# uLI-00.net
KiCad netlist of a schematic drawn in EAGLE
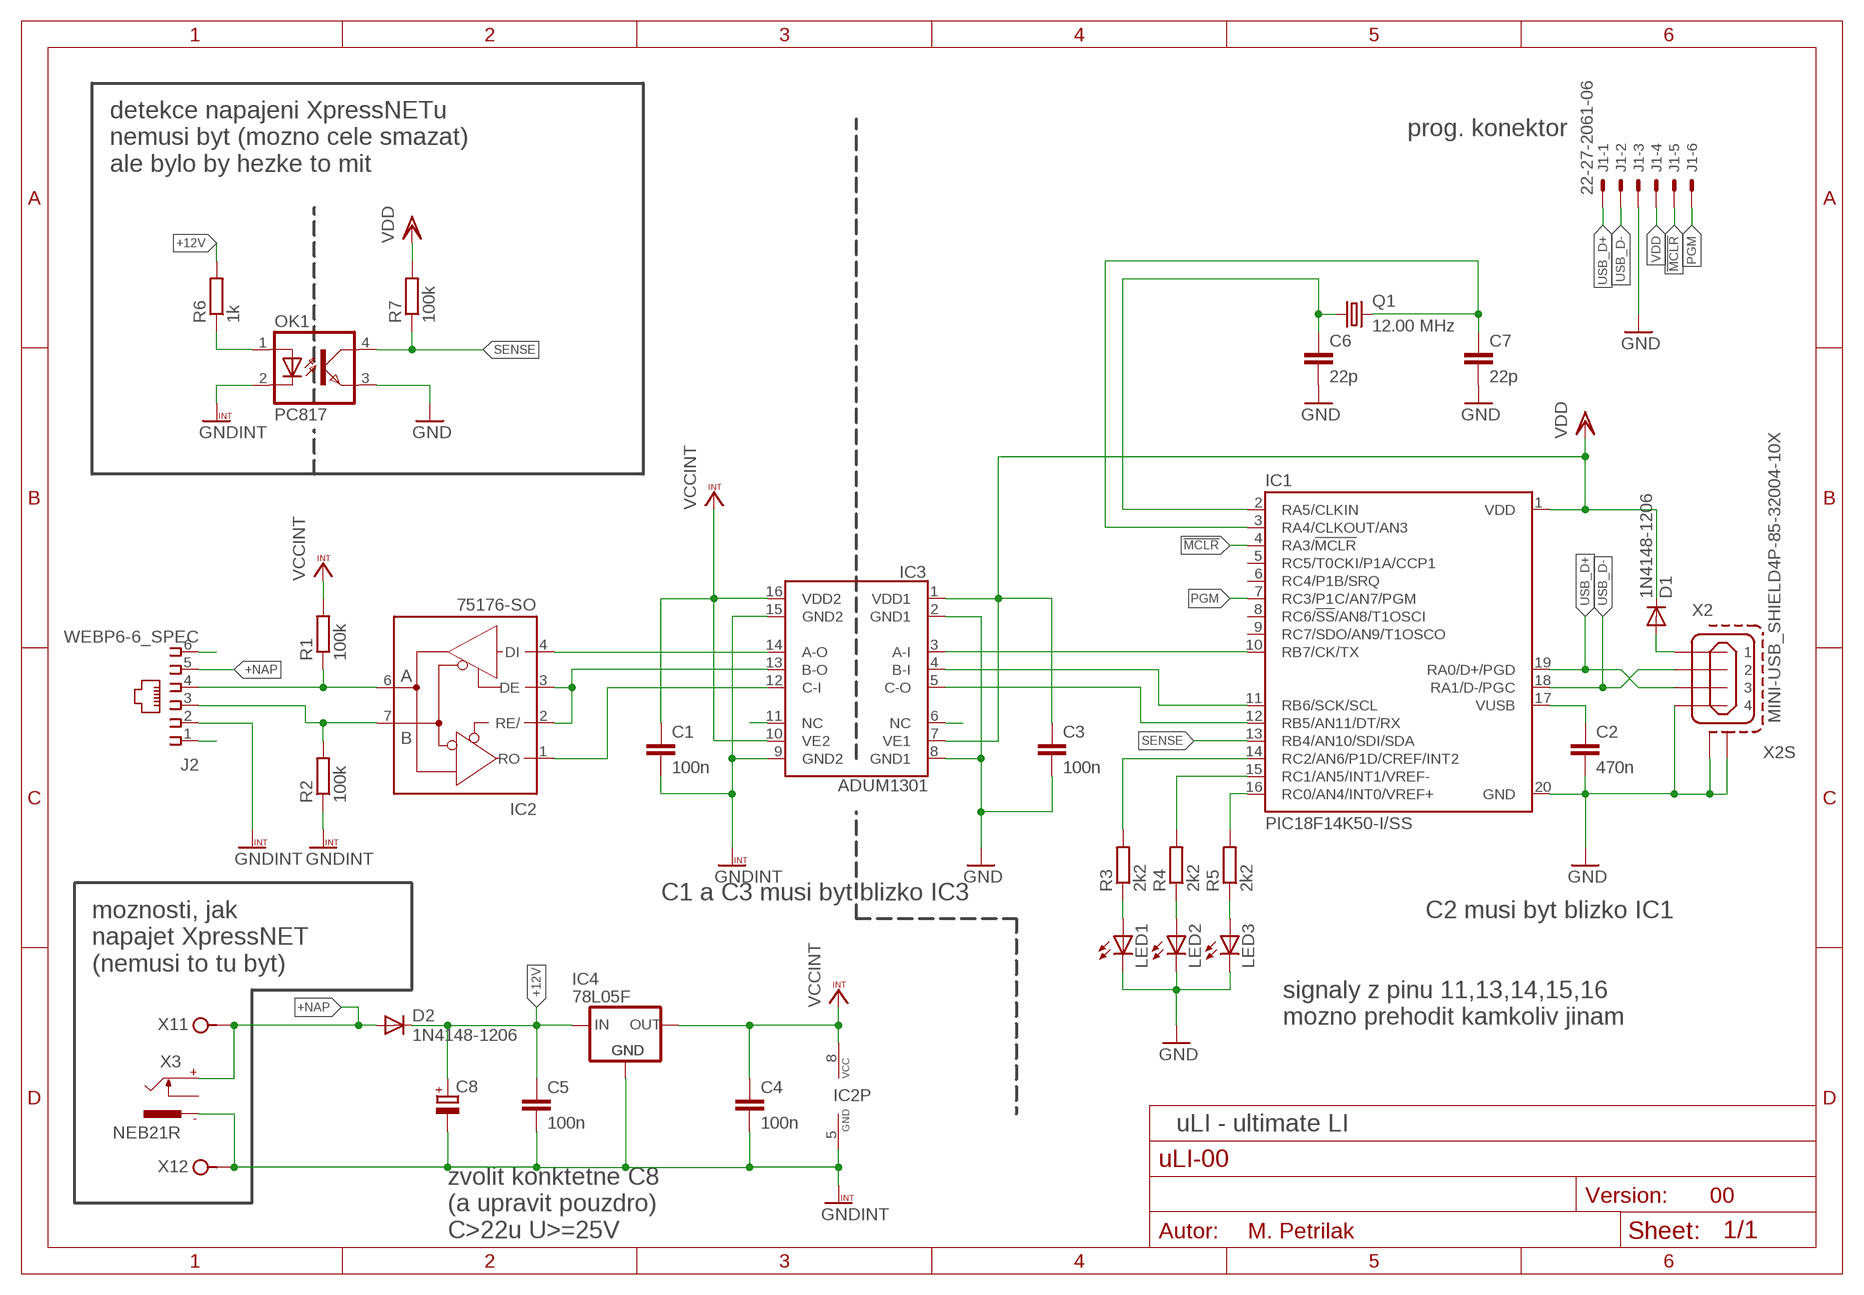
[diagram p0: schematic, sheet 1]

(export (version "E")
  (design (tool "Eeschema 10.0.6"))
  (components
    (comp (ref "C1")
      (value "100n")
      (footprint "eagle-import:C1206")
      (libsource (lib "eagle-import") (part "C-EUC1206"))
    )
    (comp (ref "C2")
      (value "470n")
      (footprint "eagle-import:C1206")
      (libsource (lib "eagle-import") (part "C-EUC1206"))
    )
    (comp (ref "C3")
      (value "100n")
      (footprint "eagle-import:C1206")
      (libsource (lib "eagle-import") (part "C-EUC1206"))
    )
    (comp (ref "C4")
      (value "100n")
      (footprint "eagle-import:C1206")
      (libsource (lib "eagle-import") (part "C-EUC1206"))
    )
    (comp (ref "C5")
      (value "100n")
      (footprint "eagle-import:C1206")
      (libsource (lib "eagle-import") (part "C-EUC1206"))
    )
    (comp (ref "C6")
      (value "22p")
      (footprint "eagle-import:C0805")
      (libsource (lib "eagle-import") (part "C-EUC0805"))
    )
    (comp (ref "C7")
      (value "22p")
      (footprint "eagle-import:C0805")
      (libsource (lib "eagle-import") (part "C-EUC0805"))
    )
    (comp (ref "C8")
      (value "CPOL-EUE3.5-8L")
      (footprint "eagle-import:E3,5-8L")
      (libsource (lib "eagle-import") (part "CPOL-EUE3.5-8L"))
    )
    (comp (ref "D1")
      (value "1N4148-1206")
      (footprint "eagle-import:D1206")
      (libsource (lib "eagle-import") (part "1N4148-1206"))
    )
    (comp (ref "D2")
      (value "1N4148-1206")
      (footprint "eagle-import:D1206")
      (libsource (lib "eagle-import") (part "1N4148-1206"))
    )
    (comp (ref "IC1")
      (value "PIC18F14K50-I/SS")
      (footprint "eagle-import:SSOP20")
      (libsource (lib "eagle-import") (part "PIC18K50-I/SSF14"))
    )
    (comp (ref "IC2")
      (value "75176-SO")
      (footprint "eagle-import:SO08")
      (libsource (lib "eagle-import") (part "75176-SO"))
    )
    (comp (ref "IC3")
      (value "ADUM1301")
      (footprint "eagle-import:SO-16W")
      (libsource (lib "eagle-import") (part "ADUM1301"))
    )
    (comp (ref "IC4")
      (value "78L05F")
      (footprint "eagle-import:SOT89")
      (libsource (lib "eagle-import") (part "78LF05"))
    )
    (comp (ref "J1")
      (value "22-27-2061-06")
      (footprint "eagle-import:6410-06")
      (libsource (lib "eagle-import") (part "22-?-0627-2061"))
    )
    (comp (ref "J2")
      (value "WEBP6-6_SPEC")
      (footprint "eagle-import:WEBP6-6_SPEC")
      (libsource (lib "eagle-import") (part "WEBP6-6_SPEC"))
    )
    (comp (ref "LED1")
      (value "LED3MM")
      (footprint "eagle-import:LED3MM")
      (libsource (lib "eagle-import") (part "LED3MM"))
    )
    (comp (ref "LED2")
      (value "LED3MM")
      (footprint "eagle-import:LED3MM")
      (libsource (lib "eagle-import") (part "LED3MM"))
    )
    (comp (ref "LED3")
      (value "LED3MM")
      (footprint "eagle-import:LED3MM")
      (libsource (lib "eagle-import") (part "LED3MM"))
    )
    (comp (ref "OK1")
      (value "PC817")
      (footprint "eagle-import:DIL04")
      (libsource (lib "eagle-import") (part "PC817"))
    )
    (comp (ref "Q1")
      (value "12.00 MHz")
      (footprint "eagle-import:HC49U70")
      (libsource (lib "eagle-import") (part "XTAL"))
    )
    (comp (ref "R1")
      (value "100k")
      (footprint "eagle-import:R1206")
      (libsource (lib "eagle-import") (part "R-EU_R1206"))
    )
    (comp (ref "R2")
      (value "100k")
      (footprint "eagle-import:R1206")
      (libsource (lib "eagle-import") (part "R-EU_R1206"))
    )
    (comp (ref "R3")
      (value "2k2")
      (footprint "eagle-import:R1206")
      (libsource (lib "eagle-import") (part "R-EU_R1206"))
    )
    (comp (ref "R4")
      (value "2k2")
      (footprint "eagle-import:R1206")
      (libsource (lib "eagle-import") (part "R-EU_R1206"))
    )
    (comp (ref "R5")
      (value "2k2")
      (footprint "eagle-import:R1206")
      (libsource (lib "eagle-import") (part "R-EU_R1206"))
    )
    (comp (ref "R6")
      (value "1k")
      (footprint "eagle-import:R1206")
      (libsource (lib "eagle-import") (part "R-EU_R1206"))
    )
    (comp (ref "R7")
      (value "100k")
      (footprint "eagle-import:R1206")
      (libsource (lib "eagle-import") (part "R-EU_R1206"))
    )
    (comp (ref "X1")
      (value "ARK1550/2")
      (footprint "eagle-import:ARK1550_2")
      (libsource (lib "eagle-import") (part "ARK1550/2"))
    )
    (comp (ref "X2")
      (value "MINI-USB_SHIELD4P-85-32004-10X")
      (footprint "eagle-import:85-32004-10X")
      (libsource (lib "eagle-import") (part "MINI-USB_SHIELD4P-85-32004-10X"))
    )
    (comp (ref "X3")
      (value "NEB21R")
      (footprint "eagle-import:NEB21R")
      (libsource (lib "eagle-import") (part "NEB21R"))
    )
  )
  (nets
    (net (code "1") (name "+12V") (class "Default")
      (node (ref "C5") (pin "1") (pinfunction "1_1") (pintype "passive"))
      (node (ref "C8") (pin "+") (pinfunction "+_+") (pintype "passive"))
      (node (ref "D2") (pin "C") (pinfunction "C_C") (pintype "passive"))
      (node (ref "IC4") (pin "3") (pinfunction "VI_3") (pintype "input"))
      (node (ref "R6") (pin "2") (pinfunction "2_2") (pintype "passive"))
    )
    (net (code "2") (name "+NAP") (class "Default")
      (node (ref "D2") (pin "A") (pinfunction "A_A") (pintype "passive"))
      (node (ref "J2") (pin "5") (pinfunction "5_5") (pintype "passive"))
      (node (ref "X1") (pin "1") (pinfunction "1_1") (pintype "passive"))
      (node (ref "X3") (pin "+") (pinfunction "+_+") (pintype "passive"))
    )
    (net (code "3") (name "/~{MCLR}") (class "Default")
      (node (ref "IC1") (pin "4") (pinfunction "RA3/~{MCLR}_4") (pintype "bidirectional"))
      (node (ref "J1") (pin "5") (pinfunction "S_5") (pintype "passive"))
    )
    (net (code "4") (name "GND") (class "Default")
      (node (ref "C2") (pin "2") (pinfunction "2_2") (pintype "passive"))
      (node (ref "C3") (pin "2") (pinfunction "2_2") (pintype "passive"))
      (node (ref "C6") (pin "2") (pinfunction "2_2") (pintype "passive"))
      (node (ref "C7") (pin "2") (pinfunction "2_2") (pintype "passive"))
      (node (ref "IC1") (pin "20") (pinfunction "GND_20") (pintype "power_in"))
      (node (ref "IC3") (pin "2") (pinfunction "GND1_2") (pintype "power_in"))
      (node (ref "IC3") (pin "8") (pinfunction "GND1_8") (pintype "power_in"))
      (node (ref "J1") (pin "3") (pinfunction "S_3") (pintype "passive"))
      (node (ref "LED1") (pin "K") (pinfunction "C_K") (pintype "passive"))
      (node (ref "LED2") (pin "K") (pinfunction "C_K") (pintype "passive"))
      (node (ref "LED3") (pin "K") (pinfunction "C_K") (pintype "passive"))
      (node (ref "OK1") (pin "3") (pinfunction "EMIT_3") (pintype "passive"))
      (node (ref "X2") (pin "4") (pinfunction "4_4") (pintype "passive"))
      (node (ref "X2") (pin "M1") (pinfunction "S1_M1") (pintype "passive"))
      (node (ref "X2") (pin "M2") (pinfunction "S2_M2") (pintype "passive"))
    )
    (net (code "5") (name "GNDINT") (class "Default")
      (node (ref "C1") (pin "2") (pinfunction "2_2") (pintype "passive"))
      (node (ref "C4") (pin "2") (pinfunction "2_2") (pintype "passive"))
      (node (ref "C5") (pin "2") (pinfunction "2_2") (pintype "passive"))
      (node (ref "C8") (pin "-") (pinfunction "-_-") (pintype "passive"))
      (node (ref "IC2") (pin "5") (pinfunction "GND_5") (pintype "power_in"))
      (node (ref "IC3") (pin "15") (pinfunction "GND2_15") (pintype "power_in"))
      (node (ref "IC3") (pin "9") (pinfunction "GND2_9") (pintype "power_in"))
      (node (ref "IC4") (pin "2") (pinfunction "GND_2") (pintype "passive"))
      (node (ref "IC4") (pin "2@1") (pinfunction "GND_2@1") (pintype "passive"))
      (node (ref "J2") (pin "2") (pinfunction "2_2") (pintype "passive"))
      (node (ref "OK1") (pin "2") (pinfunction "C_2") (pintype "passive"))
      (node (ref "R2") (pin "1") (pinfunction "1_1") (pintype "passive"))
      (node (ref "X1") (pin "2") (pinfunction "1_2") (pintype "passive"))
      (node (ref "X3") (pin "-") (pinfunction "-_-") (pintype "passive"))
    )
    (net (code "6") (name "Net-(D1-PadA)") (class "Default")
      (node (ref "D1") (pin "A") (pinfunction "A_A") (pintype "passive"))
      (node (ref "X2") (pin "1") (pinfunction "1_1") (pintype "passive"))
    )
    (net (code "7") (name "Net-(IC1-RA4{slash}CLKOUT{slash}AN3)") (class "Default")
      (node (ref "C7") (pin "1") (pinfunction "1_1") (pintype "passive"))
      (node (ref "IC1") (pin "3") (pinfunction "RA4/CLKOUT/AN3_3") (pintype "bidirectional"))
      (node (ref "Q1") (pin "2") (pinfunction "2_2") (pintype "passive"))
    )
    (net (code "8") (name "Net-(IC1-RA5{slash}CLKIN)") (class "Default")
      (node (ref "C6") (pin "1") (pinfunction "1_1") (pintype "passive"))
      (node (ref "IC1") (pin "2") (pinfunction "RA5/CLKIN_2") (pintype "bidirectional"))
      (node (ref "Q1") (pin "1") (pinfunction "1_1") (pintype "passive"))
    )
    (net (code "9") (name "Net-(IC1-RB5{slash}AN11{slash}DT{slash}RX)") (class "Default")
      (node (ref "IC1") (pin "12") (pinfunction "RB5/AN11/DT/RX_12") (pintype "bidirectional"))
      (node (ref "IC3") (pin "5") (pinfunction "C-O_5") (pintype "output"))
    )
    (net (code "10") (name "Net-(IC1-RB6{slash}SCK{slash}SCL)") (class "Default")
      (node (ref "IC1") (pin "11") (pinfunction "RB6/SCK/SCL_11") (pintype "bidirectional"))
      (node (ref "IC3") (pin "4") (pinfunction "B-I_4") (pintype "input"))
    )
    (net (code "11") (name "Net-(IC1-RB7{slash}CK{slash}TX)") (class "Default")
      (node (ref "IC1") (pin "10") (pinfunction "RB7/CK/TX_10") (pintype "bidirectional"))
      (node (ref "IC3") (pin "3") (pinfunction "A-I_3") (pintype "input"))
    )
    (net (code "12") (name "Net-(IC1-RC0{slash}AN4{slash}INT0{slash}VREF+)") (class "Default")
      (node (ref "IC1") (pin "16") (pinfunction "RC0/AN4/INT0/VREF+_16") (pintype "bidirectional"))
      (node (ref "R5") (pin "2") (pinfunction "2_2") (pintype "passive"))
    )
    (net (code "13") (name "Net-(IC1-RC1{slash}AN5{slash}INT1{slash}VREF-)") (class "Default")
      (node (ref "IC1") (pin "15") (pinfunction "RC1/AN5/INT1/VREF-_15") (pintype "bidirectional"))
      (node (ref "R4") (pin "2") (pinfunction "2_2") (pintype "passive"))
    )
    (net (code "14") (name "Net-(IC1-RC2{slash}AN6{slash}P1D{slash}CREF{slash}INT2)") (class "Default")
      (node (ref "IC1") (pin "14") (pinfunction "RC2/AN6/P1D/CREF/INT2_14") (pintype "bidirectional"))
      (node (ref "R3") (pin "2") (pinfunction "2_2") (pintype "passive"))
    )
    (net (code "15") (name "Net-(IC1-VUSB)") (class "Default")
      (node (ref "C2") (pin "1") (pinfunction "1_1") (pintype "passive"))
      (node (ref "IC1") (pin "17") (pinfunction "VUSB_17") (pintype "bidirectional"))
    )
    (net (code "16") (name "Net-(IC2A-A)") (class "Default")
      (node (ref "IC2") (pin "6") (pinfunction "A_6") (pintype "passive"))
      (node (ref "J2") (pin "4") (pinfunction "4_4") (pintype "passive"))
      (node (ref "R1") (pin "1") (pinfunction "1_1") (pintype "passive"))
    )
    (net (code "17") (name "Net-(IC2A-B)") (class "Default")
      (node (ref "IC2") (pin "7") (pinfunction "B_7") (pintype "passive"))
      (node (ref "J2") (pin "3") (pinfunction "3_3") (pintype "passive"))
      (node (ref "R2") (pin "2") (pinfunction "2_2") (pintype "passive"))
    )
    (net (code "18") (name "Net-(IC2A-DE)") (class "Default")
      (node (ref "IC2") (pin "2") (pinfunction "RE/_2") (pintype "input"))
      (node (ref "IC2") (pin "3") (pinfunction "DE_3") (pintype "input"))
      (node (ref "IC3") (pin "13") (pinfunction "B-O_13") (pintype "output"))
    )
    (net (code "19") (name "Net-(IC2A-DI)") (class "Default")
      (node (ref "IC2") (pin "4") (pinfunction "DI_4") (pintype "input"))
      (node (ref "IC3") (pin "14") (pinfunction "A-O_14") (pintype "output"))
    )
    (net (code "20") (name "Net-(IC2A-RO)") (class "Default")
      (node (ref "IC2") (pin "1") (pinfunction "RO_1") (pintype "output"))
      (node (ref "IC3") (pin "12") (pinfunction "C-I_12") (pintype "input"))
    )
    (net (code "21") (name "Net-(LED1-PadA)") (class "Default")
      (node (ref "LED1") (pin "A") (pinfunction "A_A") (pintype "passive"))
      (node (ref "R3") (pin "1") (pinfunction "1_1") (pintype "passive"))
    )
    (net (code "22") (name "Net-(LED2-PadA)") (class "Default")
      (node (ref "LED2") (pin "A") (pinfunction "A_A") (pintype "passive"))
      (node (ref "R4") (pin "1") (pinfunction "1_1") (pintype "passive"))
    )
    (net (code "23") (name "Net-(LED3-PadA)") (class "Default")
      (node (ref "LED3") (pin "A") (pinfunction "A_A") (pintype "passive"))
      (node (ref "R5") (pin "1") (pinfunction "1_1") (pintype "passive"))
    )
    (net (code "24") (name "Net-(OK1-A)") (class "Default")
      (node (ref "OK1") (pin "1") (pinfunction "A_1") (pintype "passive"))
      (node (ref "R6") (pin "1") (pinfunction "1_1") (pintype "passive"))
    )
    (net (code "25") (name "PGM") (class "Default")
      (node (ref "IC1") (pin "7") (pinfunction "RC3/P1C/AN7/PGM_7") (pintype "bidirectional"))
      (node (ref "J1") (pin "6") (pinfunction "S_6") (pintype "passive"))
    )
    (net (code "26") (name "SENSE") (class "Default")
      (node (ref "IC1") (pin "13") (pinfunction "RB4/AN10/SDI/SDA_13") (pintype "bidirectional"))
      (node (ref "OK1") (pin "4") (pinfunction "COL_4") (pintype "passive"))
      (node (ref "R7") (pin "1") (pinfunction "1_1") (pintype "passive"))
    )
    (net (code "27") (name "USB_D+") (class "Default")
      (node (ref "IC1") (pin "19") (pinfunction "RA0/D+/PGD_19") (pintype "bidirectional"))
      (node (ref "J1") (pin "1") (pinfunction "S_1") (pintype "passive"))
      (node (ref "X2") (pin "3") (pinfunction "3_3") (pintype "passive"))
    )
    (net (code "28") (name "USB_D-") (class "Default")
      (node (ref "IC1") (pin "18") (pinfunction "RA1/D-/PGC_18") (pintype "bidirectional"))
      (node (ref "J1") (pin "2") (pinfunction "S_2") (pintype "passive"))
      (node (ref "X2") (pin "2") (pinfunction "2_2") (pintype "passive"))
    )
    (net (code "29") (name "VCCINT") (class "Default")
      (node (ref "C1") (pin "1") (pinfunction "1_1") (pintype "passive"))
      (node (ref "C4") (pin "1") (pinfunction "1_1") (pintype "passive"))
      (node (ref "IC2") (pin "8") (pinfunction "VCC_8") (pintype "power_in"))
      (node (ref "IC3") (pin "10") (pinfunction "VE2_10") (pintype "input"))
      (node (ref "IC3") (pin "16") (pinfunction "VDD2_16") (pintype "power_in"))
      (node (ref "IC4") (pin "1") (pinfunction "VO_1") (pintype "passive"))
      (node (ref "R1") (pin "2") (pinfunction "2_2") (pintype "passive"))
    )
    (net (code "30") (name "VDD") (class "Default")
      (node (ref "C3") (pin "1") (pinfunction "1_1") (pintype "passive"))
      (node (ref "D1") (pin "C") (pinfunction "C_C") (pintype "passive"))
      (node (ref "IC1") (pin "1") (pinfunction "VDD_1") (pintype "power_in"))
      (node (ref "IC3") (pin "1") (pinfunction "VDD1_1") (pintype "power_in"))
      (node (ref "IC3") (pin "7") (pinfunction "VE1_7") (pintype "input"))
      (node (ref "J1") (pin "4") (pinfunction "S_4") (pintype "passive"))
      (node (ref "R7") (pin "2") (pinfunction "2_2") (pintype "passive"))
    )
    (net (code "31") (name "unconnected-(IC1-RC4{slash}P1B{slash}SRQ-Pad6)") (class "Default")
      (node (ref "IC1") (pin "6") (pinfunction "RC4/P1B/SRQ_6") (pintype "bidirectional"))
    )
    (net (code "32") (name "unconnected-(IC1-RC5{slash}T0CKI{slash}P1A{slash}CCP1-Pad5)") (class "Default")
      (node (ref "IC1") (pin "5") (pinfunction "RC5/T0CKI/P1A/CCP1_5") (pintype "bidirectional"))
    )
    (net (code "33") (name "unconnected-(IC1-RC6{slash}~{SS}{slash}AN8{slash}T1OSCI-Pad8)") (class "Default")
      (node (ref "IC1") (pin "8") (pinfunction "RC6/~{SS}/AN8/T1OSCI_8") (pintype "bidirectional"))
    )
    (net (code "34") (name "unconnected-(IC1-RC7{slash}SDO{slash}AN9{slash}T1OSCO-Pad9)") (class "Default")
      (node (ref "IC1") (pin "9") (pinfunction "RC7/SDO/AN9/T1OSCO_9") (pintype "bidirectional"))
    )
    (net (code "35") (name "unconnected-(IC3-NC-Pad6)") (class "Default")
      (node (ref "IC3") (pin "6") (pinfunction "NC_6") (pintype "passive"))
    )
    (net (code "36") (name "unconnected-(IC3-NC-Pad11)") (class "Default")
      (node (ref "IC3") (pin "11") (pinfunction "NC_11") (pintype "passive"))
    )
    (net (code "37") (name "unconnected-(J2-Pad1)") (class "Default")
      (node (ref "J2") (pin "1") (pinfunction "1_1") (pintype "passive"))
    )
    (net (code "38") (name "unconnected-(J2-Pad6)") (class "Default")
      (node (ref "J2") (pin "6") (pinfunction "6_6") (pintype "passive"))
    )
    (net (code "39") (name "unconnected-(X3-PadC)") (class "Default")
      (node (ref "X3") (pin "C") (pinfunction "C_C") (pintype "passive"))
    )
  )
)
